# PowerSrc.net
KiCad netlist of a schematic drawn in Altium Designer
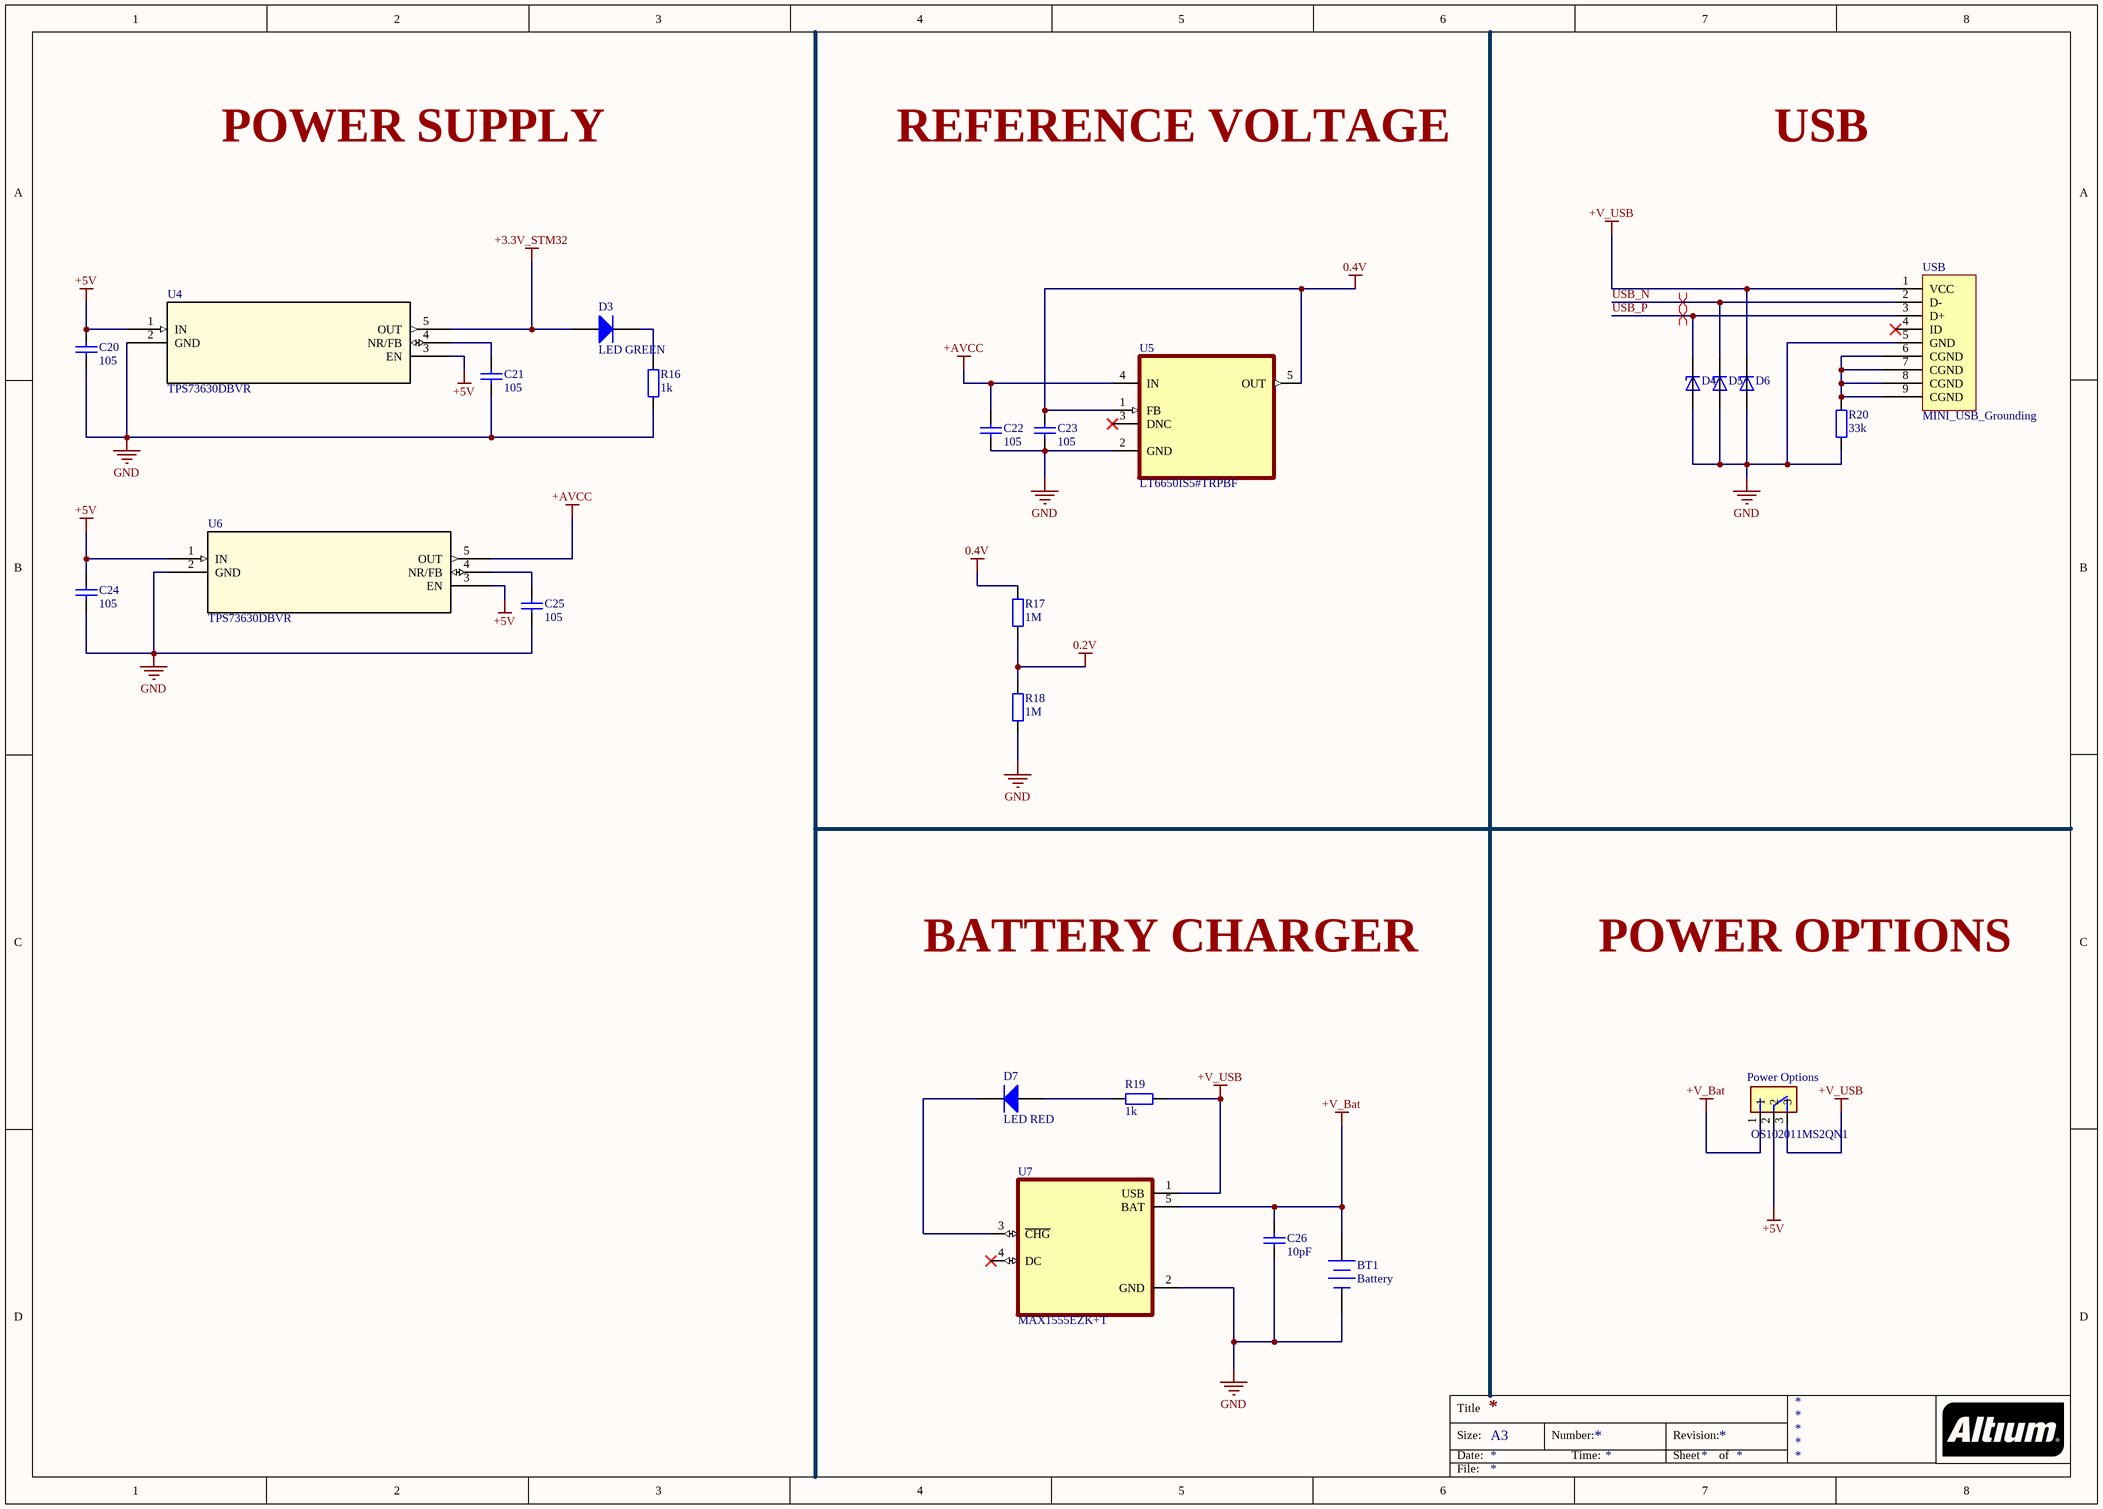
[diagram p0: PowerSrc.SchDoc]

(export (version "E")
  (design (tool "Eeschema 10.0.6"))
  (components
    (comp (ref "BT1")
      (value "Battery")
      (footprint "BAT-2")
      (description "Multicell Battery")
      (fields (field (name "PUBLISHER") "Altium Limited"))
      (libsource (lib "Miscellaneous Devices") (part "Battery"))
    )
    (comp (ref "C20")
      (value "105")
      (footprint "tu 0603")
      (description "Dán")
      (libsource (lib "Altium_Lib_by_KhueNguyenCreator") (part "Tu 0603 105 16V 20%"))
    )
    (comp (ref "C21")
      (value "105")
      (footprint "tu 0603")
      (description "Dán")
      (libsource (lib "Altium_Lib_by_KhueNguyenCreator") (part "Tu 0603 105 16V 20%"))
    )
    (comp (ref "C22")
      (value "105")
      (footprint "tu 0603")
      (description "Dán")
      (libsource (lib "Altium_Lib_by_KhueNguyenCreator") (part "Tu 0603 105 16V 20%"))
    )
    (comp (ref "C23")
      (value "105")
      (footprint "tu 0603")
      (description "Dán")
      (libsource (lib "Altium_Lib_by_KhueNguyenCreator") (part "Tu 0603 105 16V 20%"))
    )
    (comp (ref "C24")
      (value "105")
      (footprint "tu 0603")
      (description "Dán")
      (libsource (lib "Altium_Lib_by_KhueNguyenCreator") (part "Tu 0603 105 16V 20%"))
    )
    (comp (ref "C25")
      (value "105")
      (footprint "tu 0603")
      (description "Dán")
      (libsource (lib "Altium_Lib_by_KhueNguyenCreator") (part "Tu 0603 105 16V 20%"))
    )
    (comp (ref "C26")
      (value "10pF")
      (footprint "tu 0805")
      (description "Dán")
      (libsource (lib "Altium_Lib_by_KhueNguyenCreator") (part "Tu 0805 10pF 50V 10%"))
    )
    (comp (ref "D3")
      (value "LED GREEN")
      (footprint "J1-0603")
      (description "Default Diode")
      (fields (field (name "PUBLISHER") "Altium Limited"))
      (libsource (lib "MSP430_sch_1060821") (part "Diode"))
    )
    (comp (ref "D4")
      (value "AVRL161A1R1NTA")
      (footprint "AVRL161A1R1NTA:TVS_AVRL161A1R1NTA")
      (fields (field (name "MF") "{'manufacturer': u'TDK'}"))
      (libsource (lib "*") (part "AVRL161A1R1NTA"))
    )
    (comp (ref "D5")
      (value "AVRL161A1R1NTA")
      (footprint "AVRL161A1R1NTA:TVS_AVRL161A1R1NTA")
      (fields (field (name "MF") "{'manufacturer': u'TDK'}"))
      (libsource (lib "*") (part "AVRL161A1R1NTA"))
    )
    (comp (ref "D6")
      (value "AVRL161A1R1NTA")
      (footprint "AVRL161A1R1NTA:TVS_AVRL161A1R1NTA")
      (fields (field (name "MF") "{'manufacturer': u'TDK'}"))
      (libsource (lib "*") (part "AVRL161A1R1NTA"))
    )
    (comp (ref "D7")
      (value "LED RED")
      (footprint "J1-0603")
      (description "Default Diode")
      (fields (field (name "PUBLISHER") "Altium Limited"))
      (libsource (lib "MSP430_sch_1060821") (part "Diode"))
    )
    (comp (ref "Power Options")
      (value "OS102011MS2QN1")
      (footprint "OS102011MS2QN1:SW_OS102011MS2QN1")
      (description "Switch Slide ON ON SPDT Top Slide 0.1A 12VDC 10000Cycles PC Pins Thru-Hole Bulk")
      (fields (field (name "MF") "{'manufacturer': u'C&K'}"))
      (libsource (lib "*") (part "OS102011MS2QN1"))
    )
    (comp (ref "R16")
      (value "1k")
      (footprint "tro smd 0603")
      (description "Dán")
      (libsource (lib "Altium_Lib_by_KhueNguyenCreator") (part "Tro 0603 5% 1k"))
    )
    (comp (ref "R17")
      (value "1M")
      (footprint "tro smd 0603")
      (description "Dán")
      (libsource (lib "Altium_Lib_by_KhueNguyenCreator") (part "Tro 0603 5% 1M"))
    )
    (comp (ref "R18")
      (value "1M")
      (footprint "tro smd 0603")
      (description "Dán")
      (libsource (lib "Altium_Lib_by_KhueNguyenCreator") (part "Tro 0603 5% 1M"))
    )
    (comp (ref "R19")
      (value "1k")
      (footprint "tro smd 0603")
      (description "Dán")
      (libsource (lib "Altium_Lib_by_KhueNguyenCreator") (part "Tro 0603 1% 1k"))
    )
    (comp (ref "R20")
      (value "33k")
      (footprint "Tro smd 0603")
      (description "Dán")
      (libsource (lib "Altium_Lib_by_KhueNguyenCreator") (part "Tro 0603 1% 33k"))
    )
    (comp (ref "U4")
      (value "TPS73630DBVR")
      (footprint "DBV5-M")
      (description "No Description Available")
      (libsource (lib "TPS73630DBVR") (part "TPS73630DBVR"))
    )
    (comp (ref "U5")
      (value "LT6650IS5#TRPBF")
      (footprint "LT6650IS5#TRPBF:SOT95P280X100-5N")
      (description "Micropower, 400mV Reference with Rail-to-Rail Buffer Amplifier")
      (fields (field (name "MF") "{'manufacturer': u'Analog Devices'}"))
      (libsource (lib "*") (part "LT6650IS5#TRPBF"))
    )
    (comp (ref "U6")
      (value "TPS73630DBVR")
      (footprint "DBV5-M")
      (description "No Description Available")
      (libsource (lib "TPS73630DBVR") (part "TPS73630DBVR"))
    )
    (comp (ref "U7")
      (value "MAX1555EZK+T")
      (footprint "MAX1555EZK+T:SOT95P275X110-5N")
      (fields (field (name "MF") "{'manufacturer': u'Analog Devices'}"))
      (libsource (lib "*") (part "MAX1555EZK+T"))
    )
    (comp (ref "USB")
      (value "MINI_USB_Grounding")
      (footprint "micro_USB shilding")
      (libsource (lib "MSP430_sch_1061121") (part "MINI_USB_Grounding"))
    )
  )
  (nets
    (net (code "1") (name "+3.3V_STM32") (class "Default")
      (node (ref "D3") (pin "1") (pinfunction "A_1") (pintype "passive"))
      (node (ref "U4") (pin "5") (pinfunction "OUT_5") (pintype "output"))
    )
    (net (code "2") (name "+5V") (class "Default")
      (node (ref "C20") (pin "1") (pinfunction "1_1") (pintype "passive"))
      (node (ref "C24") (pin "1") (pinfunction "1_1") (pintype "passive"))
      (node (ref "Power Options") (pin "2") (pinfunction "2_2") (pintype "passive"))
      (node (ref "U4") (pin "1") (pinfunction "IN_1") (pintype "input"))
      (node (ref "U4") (pin "3") (pinfunction "EN_3") (pintype "passive"))
      (node (ref "U6") (pin "1") (pinfunction "IN_1") (pintype "input"))
      (node (ref "U6") (pin "3") (pinfunction "EN_3") (pintype "passive"))
    )
    (net (code "3") (name "+AVCC") (class "Default")
      (node (ref "C22") (pin "1") (pinfunction "1_1") (pintype "passive"))
      (node (ref "U5") (pin "4") (pinfunction "IN_4") (pintype "power_in"))
      (node (ref "U6") (pin "5") (pinfunction "OUT_5") (pintype "output"))
    )
    (net (code "4") (name "+V_Bat") (class "Default")
      (node (ref "BT1") (pin "1") (pinfunction "+_1") (pintype "passive"))
      (node (ref "C26") (pin "1") (pinfunction "1_1") (pintype "passive"))
      (node (ref "Power Options") (pin "1") (pinfunction "1_1") (pintype "passive"))
      (node (ref "U7") (pin "5") (pinfunction "BAT_5") (pintype "power_in"))
    )
    (net (code "5") (name "+V_USB") (class "Default")
      (node (ref "D6") (pin "1") (pinfunction "C_1") (pintype "passive"))
      (node (ref "Power Options") (pin "3") (pinfunction "3_3") (pintype "passive"))
      (node (ref "R19") (pin "2") (pinfunction "2_2") (pintype "passive"))
      (node (ref "U7") (pin "1") (pinfunction "USB_1") (pintype "power_in"))
      (node (ref "USB") (pin "1") (pinfunction "VCC_1") (pintype "passive"))
    )
    (net (code "6") (name "/USB_N") (class "Default")
      (node (ref "D5") (pin "1") (pinfunction "C_1") (pintype "passive"))
      (node (ref "USB") (pin "2") (pinfunction "D-_2") (pintype "passive"))
    )
    (net (code "7") (name "/USB_P") (class "Default")
      (node (ref "D4") (pin "1") (pinfunction "C_1") (pintype "passive"))
      (node (ref "USB") (pin "3") (pinfunction "D+_3") (pintype "passive"))
    )
    (net (code "8") (name "0.2V") (class "Default")
      (node (ref "R17") (pin "1") (pinfunction "1_1") (pintype "passive"))
      (node (ref "R18") (pin "2") (pinfunction "2_2") (pintype "passive"))
    )
    (net (code "9") (name "0.4V") (class "Default")
      (node (ref "C23") (pin "1") (pinfunction "1_1") (pintype "passive"))
      (node (ref "R17") (pin "2") (pinfunction "2_2") (pintype "passive"))
      (node (ref "U5") (pin "1") (pinfunction "FB_1") (pintype "input"))
      (node (ref "U5") (pin "5") (pinfunction "OUT_5") (pintype "output"))
    )
    (net (code "10") (name "GND") (class "Default")
      (node (ref "BT1") (pin "2") (pinfunction "-_2") (pintype "passive"))
      (node (ref "C20") (pin "2") (pinfunction "2_2") (pintype "passive"))
      (node (ref "C21") (pin "2") (pinfunction "2_2") (pintype "passive"))
      (node (ref "C22") (pin "2") (pinfunction "2_2") (pintype "passive"))
      (node (ref "C23") (pin "2") (pinfunction "2_2") (pintype "passive"))
      (node (ref "C24") (pin "2") (pinfunction "2_2") (pintype "passive"))
      (node (ref "C25") (pin "2") (pinfunction "2_2") (pintype "passive"))
      (node (ref "C26") (pin "2") (pinfunction "2_2") (pintype "passive"))
      (node (ref "D4") (pin "2") (pinfunction "A_2") (pintype "passive"))
      (node (ref "D5") (pin "2") (pinfunction "A_2") (pintype "passive"))
      (node (ref "D6") (pin "2") (pinfunction "A_2") (pintype "passive"))
      (node (ref "R16") (pin "2") (pinfunction "2_2") (pintype "passive"))
      (node (ref "R18") (pin "1") (pinfunction "1_1") (pintype "passive"))
      (node (ref "R20") (pin "1") (pinfunction "1_1") (pintype "passive"))
      (node (ref "U4") (pin "2") (pinfunction "GND_2") (pintype "power_in"))
      (node (ref "U5") (pin "2") (pinfunction "GND_2") (pintype "passive"))
      (node (ref "U6") (pin "2") (pinfunction "GND_2") (pintype "power_in"))
      (node (ref "U7") (pin "2") (pinfunction "GND_2") (pintype "power_in"))
      (node (ref "USB") (pin "5") (pinfunction "GND_5") (pintype "passive"))
    )
    (net (code "11") (name "Net-(D3-K)") (class "Default")
      (node (ref "D3") (pin "2") (pinfunction "K_2") (pintype "passive"))
      (node (ref "R16") (pin "1") (pinfunction "1_1") (pintype "passive"))
    )
    (net (code "12") (name "Net-(D7-A)") (class "Default")
      (node (ref "D7") (pin "1") (pinfunction "A_1") (pintype "passive"))
      (node (ref "R19") (pin "1") (pinfunction "1_1") (pintype "passive"))
    )
    (net (code "13") (name "Net-(D7-K)") (class "Default")
      (node (ref "D7") (pin "2") (pinfunction "K_2") (pintype "passive"))
      (node (ref "U7") (pin "3") (pinfunction "~{CHG}_3") (pintype "bidirectional"))
    )
    (net (code "14") (name "Net-(R20-Pad2)") (class "Default")
      (node (ref "R20") (pin "2") (pinfunction "2_2") (pintype "passive"))
      (node (ref "USB") (pin "6") (pinfunction "CGND_6") (pintype "passive"))
      (node (ref "USB") (pin "7") (pinfunction "CGND_7") (pintype "passive"))
      (node (ref "USB") (pin "8") (pinfunction "CGND_8") (pintype "passive"))
      (node (ref "USB") (pin "9") (pinfunction "CGND_9") (pintype "passive"))
    )
    (net (code "15") (name "Net-(U4-NR{slash}FB)") (class "Default")
      (node (ref "C21") (pin "1") (pinfunction "1_1") (pintype "passive"))
      (node (ref "U4") (pin "4") (pinfunction "NR/FB_4") (pintype "bidirectional"))
    )
    (net (code "16") (name "Net-(U6-NR{slash}FB)") (class "Default")
      (node (ref "C25") (pin "1") (pinfunction "1_1") (pintype "passive"))
      (node (ref "U6") (pin "4") (pinfunction "NR/FB_4") (pintype "bidirectional"))
    )
    (net (code "17") (name "unconnected-(U5-DNC-Pad3)") (class "Default")
      (node (ref "U5") (pin "3") (pinfunction "DNC_3") (pintype "passive+no_connect"))
    )
    (net (code "18") (name "unconnected-(U7-DC-Pad4)") (class "Default")
      (node (ref "U7") (pin "4") (pinfunction "DC_4") (pintype "bidirectional+no_connect"))
    )
    (net (code "19") (name "unconnected-(USB-ID-Pad4)") (class "Default")
      (node (ref "USB") (pin "4") (pinfunction "ID_4") (pintype "passive+no_connect"))
    )
  )
)
